# Banker_EDGE_2_BNC.net
KiCad netlist of a schematic drawn in Altium Designer
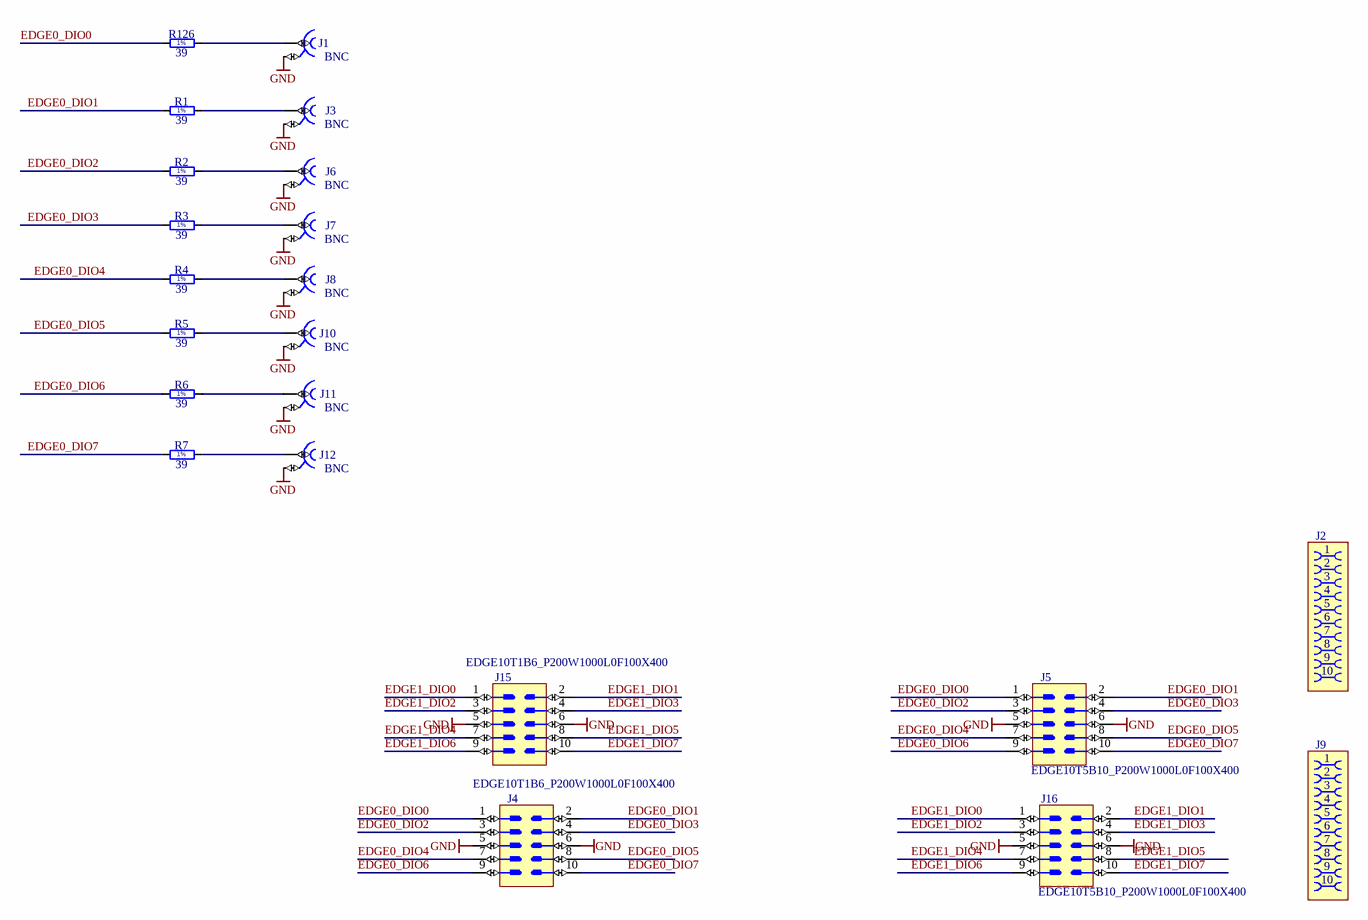
[diagram p0: Banker_EDGE_2_BNC.SchDoc]

(export (version "E")
  (design (tool "Eeschema 10.0.6"))
  (components
    (comp (ref "J1")
      (value "BNC")
      (footprint "TYCO_5-1634503-1")
      (fields
        (field (name "PART NUMBER") "TYCO_5-1634503-1")
        (field (name "MANUFACTURER") "TYCO ELECTRONICS")
        (field (name "MANUFACTURER PART NUMBER") "5-1634503-1")
      )
      (libsource (lib "*") (part "Coax_1Female_1Shield"))
    )
    (comp (ref "J2")
      (value "~")
      (footprint "AVX_00 9159 010 061 916")
      (description "Open Ended Card Edge Connector, 9159 Series")
      (fields
        (field (name "PART NUMBER") "AVX_00 9159 010 061 916")
        (field (name "MANUFACTURER") "AVX")
        (field (name "AUTHOR") "CERN DEM MR")
      )
      (libsource (lib "Connectors") (part "AVX_00 9159 010 061 916"))
    )
    (comp (ref "J3")
      (value "BNC")
      (footprint "TYCO_5-1634503-1")
      (fields
        (field (name "PART NUMBER") "TYCO_5-1634503-1")
        (field (name "MANUFACTURER") "TYCO ELECTRONICS")
        (field (name "MANUFACTURER PART NUMBER") "5-1634503-1")
      )
      (libsource (lib "*") (part "Coax_1Female_1Shield"))
    )
    (comp (ref "J4")
      (value "~")
      (footprint "EDGE10T1B6_P200W1000L0F100X400")
      (description "PCB Edge Connector 10 (2x5)")
      (fields
        (field (name "PART NUMBER") "EDGE10T1B6_P200W1000L0F100X400")
        (field (name "AUTHOR") "CERN DEM MR")
      )
      (libsource (lib "*") (part "PCB Edge Connector 10 (2x5)"))
    )
    (comp (ref "J5")
      (value "~")
      (footprint "EDGE10T5B10_P200W1000L0F100X400")
      (description "PCB Edge Connector 10 (2x5)")
      (fields
        (field (name "PART NUMBER") "EDGE10T5B10_P200W1000L0F100X400")
        (field (name "AUTHOR") "CERN DEM MR")
      )
      (libsource (lib "*") (part "PCB Edge Connector 10 (2x5)"))
    )
    (comp (ref "J6")
      (value "BNC")
      (footprint "TYCO_5-1634503-1")
      (fields
        (field (name "PART NUMBER") "TYCO_5-1634503-1")
        (field (name "MANUFACTURER") "TYCO ELECTRONICS")
        (field (name "MANUFACTURER PART NUMBER") "5-1634503-1")
      )
      (libsource (lib "*") (part "Coax_1Female_1Shield"))
    )
    (comp (ref "J7")
      (value "BNC")
      (footprint "TYCO_5-1634503-1")
      (fields
        (field (name "PART NUMBER") "TYCO_5-1634503-1")
        (field (name "MANUFACTURER") "TYCO ELECTRONICS")
        (field (name "MANUFACTURER PART NUMBER") "5-1634503-1")
      )
      (libsource (lib "*") (part "Coax_1Female_1Shield"))
    )
    (comp (ref "J8")
      (value "BNC")
      (footprint "TYCO_5-1634503-1")
      (fields
        (field (name "PART NUMBER") "TYCO_5-1634503-1")
        (field (name "MANUFACTURER") "TYCO ELECTRONICS")
        (field (name "MANUFACTURER PART NUMBER") "5-1634503-1")
      )
      (libsource (lib "*") (part "Coax_1Female_1Shield"))
    )
    (comp (ref "J9")
      (value "~")
      (footprint "AVX_00 9159 010 061 916")
      (description "Open Ended Card Edge Connector, 9159 Series")
      (fields
        (field (name "PART NUMBER") "AVX_00 9159 010 061 916")
        (field (name "MANUFACTURER") "AVX")
        (field (name "AUTHOR") "CERN DEM MR")
      )
      (libsource (lib "Connectors") (part "AVX_00 9159 010 061 916"))
    )
    (comp (ref "J10")
      (value "BNC")
      (footprint "TYCO_5-1634503-1")
      (fields
        (field (name "PART NUMBER") "TYCO_5-1634503-1")
        (field (name "MANUFACTURER") "TYCO ELECTRONICS")
        (field (name "MANUFACTURER PART NUMBER") "5-1634503-1")
      )
      (libsource (lib "*") (part "Coax_1Female_1Shield"))
    )
    (comp (ref "J11")
      (value "BNC")
      (footprint "TYCO_5-1634503-1")
      (fields
        (field (name "PART NUMBER") "TYCO_5-1634503-1")
        (field (name "MANUFACTURER") "TYCO ELECTRONICS")
        (field (name "MANUFACTURER PART NUMBER") "5-1634503-1")
      )
      (libsource (lib "*") (part "Coax_1Female_1Shield"))
    )
    (comp (ref "J12")
      (value "BNC")
      (footprint "TYCO_5-1634503-1")
      (fields
        (field (name "PART NUMBER") "TYCO_5-1634503-1")
        (field (name "MANUFACTURER") "TYCO ELECTRONICS")
        (field (name "MANUFACTURER PART NUMBER") "5-1634503-1")
      )
      (libsource (lib "*") (part "Coax_1Female_1Shield"))
    )
    (comp (ref "J15")
      (value "~")
      (footprint "EDGE10T1B6_P200W1000L0F100X400")
      (description "PCB Edge Connector 10 (2x5)")
      (fields
        (field (name "PART NUMBER") "EDGE10T1B6_P200W1000L0F100X400")
        (field (name "AUTHOR") "CERN DEM MR")
      )
      (libsource (lib "*") (part "PCB Edge Connector 10 (2x5)"))
    )
    (comp (ref "J16")
      (value "~")
      (footprint "EDGE10T5B10_P200W1000L0F100X400")
      (description "PCB Edge Connector 10 (2x5)")
      (fields
        (field (name "PART NUMBER") "EDGE10T5B10_P200W1000L0F100X400")
        (field (name "AUTHOR") "CERN DEM MR")
      )
      (libsource (lib "*") (part "PCB Edge Connector 10 (2x5)"))
    )
    (comp (ref "R1")
      (value "39")
      (footprint "RESC2012X60N")
      (description "Resistor - 1%")
      (fields
        (field (name "PART NUMBER") "R0805_39R_1%_0.125W_100PPM")
        (field (name "POWER") "0.125W")
        (field (name "AUTHOR") "CERN DEM JLC")
      )
      (libsource (lib "Resistors") (part "Resistor - 1%"))
    )
    (comp (ref "R2")
      (value "39")
      (footprint "RESC2012X60N")
      (description "Resistor - 1%")
      (fields
        (field (name "PART NUMBER") "R0805_39R_1%_0.125W_100PPM")
        (field (name "POWER") "0.125W")
        (field (name "AUTHOR") "CERN DEM JLC")
      )
      (libsource (lib "Resistors") (part "Resistor - 1%"))
    )
    (comp (ref "R3")
      (value "39")
      (footprint "RESC2012X60N")
      (description "Resistor - 1%")
      (fields
        (field (name "PART NUMBER") "R0805_39R_1%_0.125W_100PPM")
        (field (name "POWER") "0.125W")
        (field (name "AUTHOR") "CERN DEM JLC")
      )
      (libsource (lib "Resistors") (part "Resistor - 1%"))
    )
    (comp (ref "R4")
      (value "39")
      (footprint "RESC2012X60N")
      (description "Resistor - 1%")
      (fields
        (field (name "PART NUMBER") "R0805_39R_1%_0.125W_100PPM")
        (field (name "POWER") "0.125W")
        (field (name "AUTHOR") "CERN DEM JLC")
      )
      (libsource (lib "Resistors") (part "Resistor - 1%"))
    )
    (comp (ref "R5")
      (value "39")
      (footprint "RESC2012X60N")
      (description "Resistor - 1%")
      (fields
        (field (name "PART NUMBER") "R0805_39R_1%_0.125W_100PPM")
        (field (name "POWER") "0.125W")
        (field (name "AUTHOR") "CERN DEM JLC")
      )
      (libsource (lib "Resistors") (part "Resistor - 1%"))
    )
    (comp (ref "R6")
      (value "39")
      (footprint "RESC2012X60N")
      (description "Resistor - 1%")
      (fields
        (field (name "PART NUMBER") "R0805_39R_1%_0.125W_100PPM")
        (field (name "POWER") "0.125W")
        (field (name "AUTHOR") "CERN DEM JLC")
      )
      (libsource (lib "Resistors") (part "Resistor - 1%"))
    )
    (comp (ref "R7")
      (value "39")
      (footprint "RESC2012X60N")
      (description "Resistor - 1%")
      (fields
        (field (name "PART NUMBER") "R0805_39R_1%_0.125W_100PPM")
        (field (name "POWER") "0.125W")
        (field (name "AUTHOR") "CERN DEM JLC")
      )
      (libsource (lib "Resistors") (part "Resistor - 1%"))
    )
    (comp (ref "R126")
      (value "39")
      (footprint "RESC2012X60N")
      (description "Resistor - 1%")
      (fields
        (field (name "PART NUMBER") "R0805_39R_1%_0.125W_100PPM")
        (field (name "POWER") "0.125W")
        (field (name "AUTHOR") "CERN DEM JLC")
      )
      (libsource (lib "Resistors") (part "Resistor - 1%"))
    )
  )
  (nets
    (net (code "1") (name "/EDGE0_DIO0") (class "Default")
      (node (ref "J4") (pin "1") (pinfunction "1_1") (pintype "bidirectional"))
      (node (ref "J5") (pin "1") (pinfunction "1_1") (pintype "bidirectional"))
      (node (ref "R126") (pin "1") (pinfunction "1_1") (pintype "passive"))
    )
    (net (code "2") (name "/EDGE0_DIO1") (class "Default")
      (node (ref "J4") (pin "2") (pinfunction "2_2") (pintype "bidirectional"))
      (node (ref "J5") (pin "2") (pinfunction "2_2") (pintype "bidirectional"))
      (node (ref "R1") (pin "1") (pinfunction "1_1") (pintype "passive"))
    )
    (net (code "3") (name "/EDGE0_DIO2") (class "Default")
      (node (ref "J4") (pin "3") (pinfunction "3_3") (pintype "bidirectional"))
      (node (ref "J5") (pin "3") (pinfunction "3_3") (pintype "bidirectional"))
      (node (ref "R2") (pin "1") (pinfunction "1_1") (pintype "passive"))
    )
    (net (code "4") (name "/EDGE0_DIO3") (class "Default")
      (node (ref "J4") (pin "4") (pinfunction "4_4") (pintype "bidirectional"))
      (node (ref "J5") (pin "4") (pinfunction "4_4") (pintype "bidirectional"))
      (node (ref "R3") (pin "1") (pinfunction "1_1") (pintype "passive"))
    )
    (net (code "5") (name "/EDGE0_DIO4") (class "Default")
      (node (ref "J4") (pin "7") (pinfunction "7_7") (pintype "bidirectional"))
      (node (ref "J5") (pin "7") (pinfunction "7_7") (pintype "bidirectional"))
      (node (ref "R4") (pin "1") (pinfunction "1_1") (pintype "passive"))
    )
    (net (code "6") (name "/EDGE0_DIO5") (class "Default")
      (node (ref "J4") (pin "8") (pinfunction "8_8") (pintype "bidirectional"))
      (node (ref "J5") (pin "8") (pinfunction "8_8") (pintype "bidirectional"))
      (node (ref "R5") (pin "1") (pinfunction "1_1") (pintype "passive"))
    )
    (net (code "7") (name "/EDGE0_DIO6") (class "Default")
      (node (ref "J4") (pin "9") (pinfunction "9_9") (pintype "bidirectional"))
      (node (ref "J5") (pin "9") (pinfunction "9_9") (pintype "bidirectional"))
      (node (ref "R6") (pin "1") (pinfunction "1_1") (pintype "passive"))
    )
    (net (code "8") (name "/EDGE0_DIO7") (class "Default")
      (node (ref "J4") (pin "10") (pinfunction "10_10") (pintype "bidirectional"))
      (node (ref "J5") (pin "10") (pinfunction "10_10") (pintype "bidirectional"))
      (node (ref "R7") (pin "1") (pinfunction "1_1") (pintype "passive"))
    )
    (net (code "9") (name "/EDGE1_DIO0") (class "Default")
      (node (ref "J15") (pin "1") (pinfunction "1_1") (pintype "bidirectional"))
      (node (ref "J16") (pin "1") (pinfunction "1_1") (pintype "bidirectional"))
    )
    (net (code "10") (name "/EDGE1_DIO1") (class "Default")
      (node (ref "J15") (pin "2") (pinfunction "2_2") (pintype "bidirectional"))
      (node (ref "J16") (pin "2") (pinfunction "2_2") (pintype "bidirectional"))
    )
    (net (code "11") (name "/EDGE1_DIO2") (class "Default")
      (node (ref "J15") (pin "3") (pinfunction "3_3") (pintype "bidirectional"))
      (node (ref "J16") (pin "3") (pinfunction "3_3") (pintype "bidirectional"))
    )
    (net (code "12") (name "/EDGE1_DIO3") (class "Default")
      (node (ref "J15") (pin "4") (pinfunction "4_4") (pintype "bidirectional"))
      (node (ref "J16") (pin "4") (pinfunction "4_4") (pintype "bidirectional"))
    )
    (net (code "13") (name "/EDGE1_DIO4") (class "Default")
      (node (ref "J15") (pin "7") (pinfunction "7_7") (pintype "bidirectional"))
      (node (ref "J16") (pin "7") (pinfunction "7_7") (pintype "bidirectional"))
    )
    (net (code "14") (name "/EDGE1_DIO5") (class "Default")
      (node (ref "J15") (pin "8") (pinfunction "8_8") (pintype "bidirectional"))
      (node (ref "J16") (pin "8") (pinfunction "8_8") (pintype "bidirectional"))
    )
    (net (code "15") (name "/EDGE1_DIO6") (class "Default")
      (node (ref "J15") (pin "9") (pinfunction "9_9") (pintype "bidirectional"))
      (node (ref "J16") (pin "9") (pinfunction "9_9") (pintype "bidirectional"))
    )
    (net (code "16") (name "/EDGE1_DIO7") (class "Default")
      (node (ref "J15") (pin "10") (pinfunction "10_10") (pintype "bidirectional"))
      (node (ref "J16") (pin "10") (pinfunction "10_10") (pintype "bidirectional"))
    )
    (net (code "17") (name "GND") (class "Default")
      (node (ref "J1") (pin "2") (pinfunction "2_2") (pintype "bidirectional"))
      (node (ref "J10") (pin "2") (pinfunction "2_2") (pintype "bidirectional"))
      (node (ref "J11") (pin "2") (pinfunction "2_2") (pintype "bidirectional"))
      (node (ref "J12") (pin "2") (pinfunction "2_2") (pintype "bidirectional"))
      (node (ref "J15") (pin "5") (pinfunction "5_5") (pintype "bidirectional"))
      (node (ref "J15") (pin "6") (pinfunction "6_6") (pintype "bidirectional"))
      (node (ref "J16") (pin "5") (pinfunction "5_5") (pintype "bidirectional"))
      (node (ref "J16") (pin "6") (pinfunction "6_6") (pintype "bidirectional"))
      (node (ref "J3") (pin "2") (pinfunction "2_2") (pintype "bidirectional"))
      (node (ref "J4") (pin "5") (pinfunction "5_5") (pintype "bidirectional"))
      (node (ref "J4") (pin "6") (pinfunction "6_6") (pintype "bidirectional"))
      (node (ref "J5") (pin "5") (pinfunction "5_5") (pintype "bidirectional"))
      (node (ref "J5") (pin "6") (pinfunction "6_6") (pintype "bidirectional"))
      (node (ref "J6") (pin "2") (pinfunction "2_2") (pintype "bidirectional"))
      (node (ref "J7") (pin "2") (pinfunction "2_2") (pintype "bidirectional"))
      (node (ref "J8") (pin "2") (pinfunction "2_2") (pintype "bidirectional"))
    )
    (net (code "18") (name "Net-(J1-Pad1)") (class "Default")
      (node (ref "J1") (pin "1") (pinfunction "1_1") (pintype "bidirectional"))
      (node (ref "R126") (pin "2") (pinfunction "2_2") (pintype "passive"))
    )
    (net (code "19") (name "Net-(J3-Pad1)") (class "Default")
      (node (ref "J3") (pin "1") (pinfunction "1_1") (pintype "bidirectional"))
      (node (ref "R1") (pin "2") (pinfunction "2_2") (pintype "passive"))
    )
    (net (code "20") (name "Net-(J6-Pad1)") (class "Default")
      (node (ref "J6") (pin "1") (pinfunction "1_1") (pintype "bidirectional"))
      (node (ref "R2") (pin "2") (pinfunction "2_2") (pintype "passive"))
    )
    (net (code "21") (name "Net-(J7-Pad1)") (class "Default")
      (node (ref "J7") (pin "1") (pinfunction "1_1") (pintype "bidirectional"))
      (node (ref "R3") (pin "2") (pinfunction "2_2") (pintype "passive"))
    )
    (net (code "22") (name "Net-(J8-Pad1)") (class "Default")
      (node (ref "J8") (pin "1") (pinfunction "1_1") (pintype "bidirectional"))
      (node (ref "R4") (pin "2") (pinfunction "2_2") (pintype "passive"))
    )
    (net (code "23") (name "Net-(J10-Pad1)") (class "Default")
      (node (ref "J10") (pin "1") (pinfunction "1_1") (pintype "bidirectional"))
      (node (ref "R5") (pin "2") (pinfunction "2_2") (pintype "passive"))
    )
    (net (code "24") (name "Net-(J11-Pad1)") (class "Default")
      (node (ref "J11") (pin "1") (pinfunction "1_1") (pintype "bidirectional"))
      (node (ref "R6") (pin "2") (pinfunction "2_2") (pintype "passive"))
    )
    (net (code "25") (name "Net-(J12-Pad1)") (class "Default")
      (node (ref "J12") (pin "1") (pinfunction "1_1") (pintype "bidirectional"))
      (node (ref "R7") (pin "2") (pinfunction "2_2") (pintype "passive"))
    )
  )
)
